# Power_Selection_-_Power_Path.net
KiCad netlist of a schematic drawn in Altium Designer
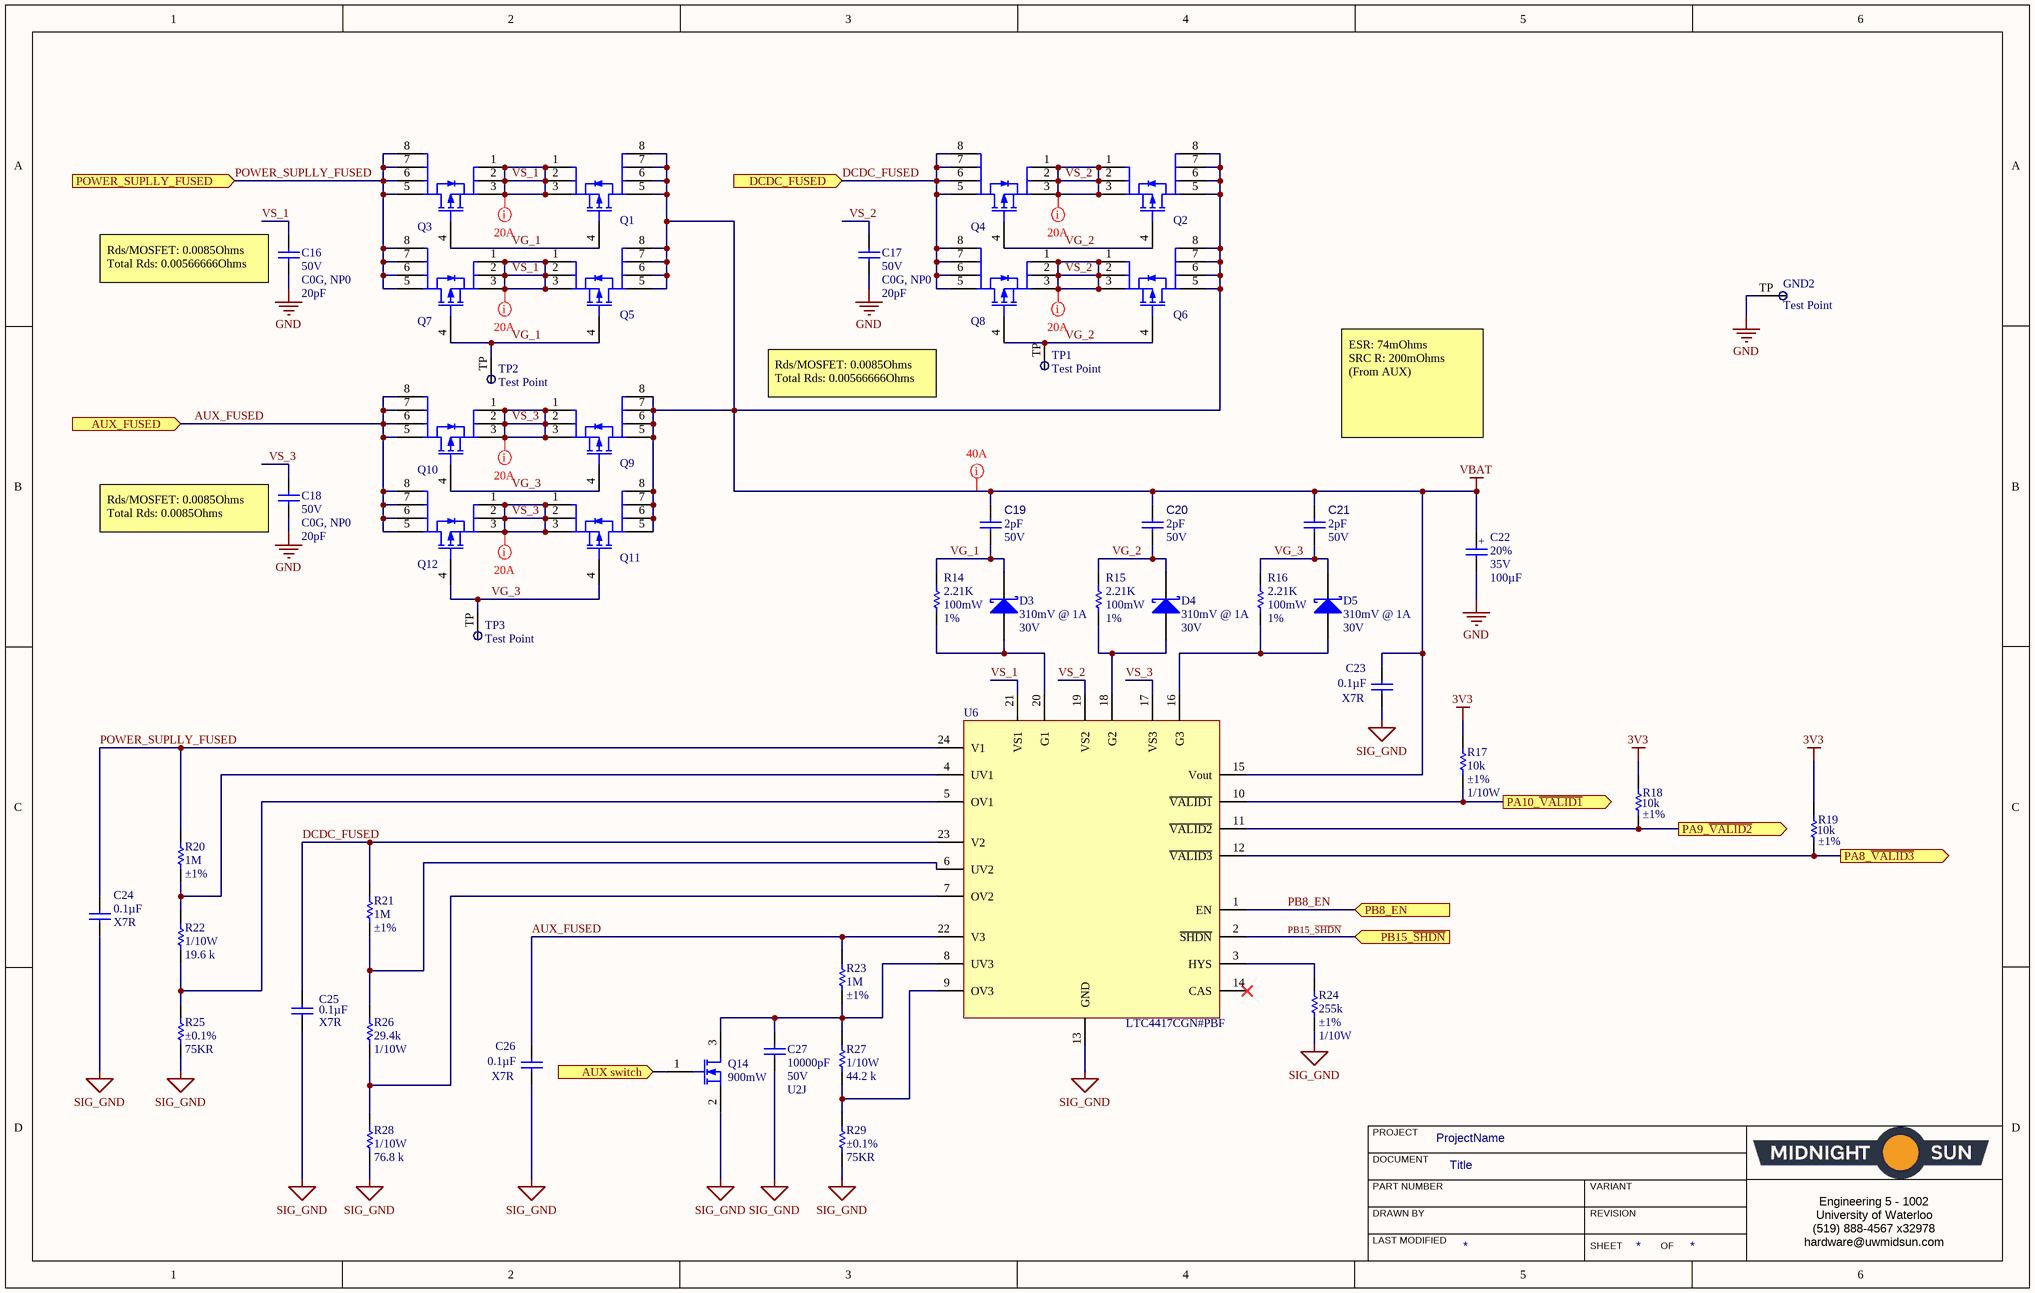
[diagram p0: Power Selection - Power Path.SchDoc]

(export (version "E")
  (design (tool "Eeschema 10.0.6"))
  (components
    (comp (ref "C16")
      (value "20pF")
      (footprint "CAP, 0603")
      (description "20pF ±5% 50V Ceramic Capacitor C0G, NP0 0603 (1608 Metric)")
      (fields
        (field (name "VOLTAGE") "50V")
        (field (name "TEMPERATURE COEFFICIENT") "C0G, NP0")
        (field (name "TOLERANCE") "5%")
        (field (name "Comment") "CAP CER 20PF 50V ±5% C0G/NP0 0603")
        (field (name "SOURCE") "Schematic Diagrams.SchLib")
      )
      (libsource (lib "University of Waterloo - Solar Car Team") (part "Symbol"))
    )
    (comp (ref "C17")
      (value "20pF")
      (footprint "CAP, 0603")
      (description "20pF ±5% 50V Ceramic Capacitor C0G, NP0 0603 (1608 Metric)")
      (fields
        (field (name "VOLTAGE") "50V")
        (field (name "TEMPERATURE COEFFICIENT") "C0G, NP0")
        (field (name "TOLERANCE") "5%")
        (field (name "Comment") "CAP CER 20PF 50V ±5% C0G/NP0 0603")
        (field (name "SOURCE") "Schematic Diagrams.SchLib")
      )
      (libsource (lib "University of Waterloo - Solar Car Team") (part "Symbol"))
    )
    (comp (ref "C18")
      (value "20pF")
      (footprint "CAP, 0603")
      (description "20pF ±5% 50V Ceramic Capacitor C0G, NP0 0603 (1608 Metric)")
      (fields
        (field (name "VOLTAGE") "50V")
        (field (name "TEMPERATURE COEFFICIENT") "C0G, NP0")
        (field (name "TOLERANCE") "5%")
        (field (name "Comment") "CAP CER 20PF 50V ±5% C0G/NP0 0603")
        (field (name "SOURCE") "Schematic Diagrams.SchLib")
      )
      (libsource (lib "University of Waterloo - Solar Car Team") (part "Symbol"))
    )
    (comp (ref "C19")
      (value "CAP CER 2PF 50V C0G 0603")
      (footprint "CAP, 0603")
      (description "2pF ±0.25pF 50V Ceramic Capacitor C0G, NP0 0603 (1608 Metric)")
      (fields (field (name "VOLTAGE RATING (DC)") "50V") (field (name "CAPACITANCE") "2pF"))
      (libsource (lib "University of Waterloo - Solar Car Team") (part "CAP-NP-2"))
    )
    (comp (ref "C20")
      (value "CAP CER 2PF 50V C0G 0603")
      (footprint "CAP, 0603")
      (description "2pF ±0.25pF 50V Ceramic Capacitor C0G, NP0 0603 (1608 Metric)")
      (fields (field (name "VOLTAGE RATING (DC)") "50V") (field (name "CAPACITANCE") "2pF"))
      (libsource (lib "University of Waterloo - Solar Car Team") (part "CAP-NP-2"))
    )
    (comp (ref "C21")
      (value "CAP CER 2PF 50V C0G 0603")
      (footprint "CAP, 0603")
      (description "2pF ±0.25pF 50V Ceramic Capacitor C0G, NP0 0603 (1608 Metric)")
      (fields (field (name "VOLTAGE RATING (DC)") "50V") (field (name "CAPACITANCE") "2pF"))
      (libsource (lib "University of Waterloo - Solar Car Team") (part "CAP-NP-2"))
    )
    (comp (ref "C22")
      (value "100µF")
      (footprint "CAP ALUM 6.3MM RADIAL SMD")
      (description "100µF 35V Aluminum Electrolytic Capacitors Radial, Can - SMD 2000 Hrs @ 85°C")
      (fields
        (field (name "TOLERANCE") "20%")
        (field (name "VOLTAGE RATING") "35V")
        (field (name "VOLTAGE") "35V")
        (field (name "Comment") "CAP ALUM 100UF 20% 35V SMD")
        (field (name "SOURCE") "Schematic Diagrams.SchLib")
      )
      (libsource (lib "") (part "Symbol_1"))
    )
    (comp (ref "C23")
      (value "CAP CER 0.1UF 50V 10% X7R 0603")
      (footprint "CAP, 0603")
      (description "0.10µF ±10% 50V Ceramic Capacitor X7R 0603 (1608 Metric)")
      (fields
        (field (name "TOLERANCE") "±10%")
        (field (name "CAPACITANCE") "0.1µF")
        (field (name "TEMPERATURE COEFFICIENT") "X7R")
        (field (name "VOLTAGE") "50V")
      )
      (libsource (lib "Schematic Diagrams") (part "CAP CER 0.1UF 50V 10% X7R 0603"))
    )
    (comp (ref "C24")
      (value "CAP CER 0.1UF 50V 10% X7R 0603")
      (footprint "CAP, 0603")
      (description "0.10µF ±10% 50V Ceramic Capacitor X7R 0603 (1608 Metric)")
      (fields
        (field (name "TOLERANCE") "±10%")
        (field (name "CAPACITANCE") "0.1µF")
        (field (name "TEMPERATURE COEFFICIENT") "X7R")
        (field (name "VOLTAGE") "50V")
      )
      (libsource (lib "Schematic Diagrams") (part "CAP CER 0.1UF 50V 10% X7R 0603"))
    )
    (comp (ref "C25")
      (value "CAP CER 0.1UF 50V 10% X7R 0603")
      (footprint "CAP, 0603")
      (description "0.10µF ±10% 50V Ceramic Capacitor X7R 0603 (1608 Metric)")
      (fields
        (field (name "TOLERANCE") "±10%")
        (field (name "CAPACITANCE") "0.1µF")
        (field (name "TEMPERATURE COEFFICIENT") "X7R")
        (field (name "VOLTAGE") "50V")
      )
      (libsource (lib "Schematic Diagrams") (part "CAP CER 0.1UF 50V 10% X7R 0603"))
    )
    (comp (ref "C26")
      (value "CAP CER 0.1UF 50V 10% X7R 0603")
      (footprint "CAP, 0603")
      (description "0.10µF ±10% 50V Ceramic Capacitor X7R 0603 (1608 Metric)")
      (fields
        (field (name "TOLERANCE") "±10%")
        (field (name "CAPACITANCE") "0.1µF")
        (field (name "TEMPERATURE COEFFICIENT") "X7R")
        (field (name "VOLTAGE") "50V")
      )
      (libsource (lib "Schematic Diagrams") (part "CAP CER 0.1UF 50V 10% X7R 0603"))
    )
    (comp (ref "C27")
      (value "CAP CER 10nF 50V 5% X7R 0603")
      (footprint "CAP, 0603")
      (description "10000pF ±5% 50V Ceramic Capacitor U2J 0603 (1608 Metric)")
      (fields
        (field (name "TOLERANCE") "±5%")
        (field (name "CAPACITANCE") "10000pF")
        (field (name "VOLTAGE") "50V")
        (field (name "TEMPERATURE COEFFICIENT") "U2J")
      )
      (libsource (lib "Schematic Diagrams") (part "CAP CER 10nF 50V 5% X7R 0603"))
    )
    (comp (ref "D3")
      (value "DIODE SCHOTTKY 30V 1A POWERDI123")
      (footprint "DIODE SCHOTTKY 30V 1A POWERDI123")
      (description "Diode Schottky 30V 1A Surface Mount PowerDI™ 123")
      (fields
        (field (name "MANUFACTURER") "Diodes Incorporated")
        (field (name "MANUFACTURER PART NUMBER") "DFLS130L-7")
        (field (name "VOLTAGE - FORWARD (VF) (MAX) @ IF") "310mV @ 1A")
        (field (name "VOLTAGE - DC REVERSE (VR) (MAX)") "30V")
      )
      (libsource (lib "Schematic Diagrams") (part "DIODE SCHOTTKY 30V 1A POWERDI123"))
    )
    (comp (ref "D4")
      (value "DIODE SCHOTTKY 30V 1A POWERDI123")
      (footprint "DIODE SCHOTTKY 30V 1A POWERDI123")
      (description "Diode Schottky 30V 1A Surface Mount PowerDI™ 123")
      (fields
        (field (name "MANUFACTURER") "Diodes Incorporated")
        (field (name "MANUFACTURER PART NUMBER") "DFLS130L-7")
        (field (name "VOLTAGE - FORWARD (VF) (MAX) @ IF") "310mV @ 1A")
        (field (name "VOLTAGE - DC REVERSE (VR) (MAX)") "30V")
      )
      (libsource (lib "Schematic Diagrams") (part "DIODE SCHOTTKY 30V 1A POWERDI123"))
    )
    (comp (ref "D5")
      (value "DIODE SCHOTTKY 30V 1A POWERDI123")
      (footprint "DIODE SCHOTTKY 30V 1A POWERDI123")
      (description "Diode Schottky 30V 1A Surface Mount PowerDI™ 123")
      (fields
        (field (name "MANUFACTURER") "Diodes Incorporated")
        (field (name "MANUFACTURER PART NUMBER") "DFLS130L-7")
        (field (name "VOLTAGE - FORWARD (VF) (MAX) @ IF") "310mV @ 1A")
        (field (name "VOLTAGE - DC REVERSE (VR) (MAX)") "30V")
      )
      (libsource (lib "Schematic Diagrams") (part "DIODE SCHOTTKY 30V 1A POWERDI123"))
    )
    (comp (ref "GND2")
      (value "Test Point")
      (footprint "Test Point")
      (libsource (lib "Schematic Diagrams") (part "Test Point"))
    )
    (comp (ref "Q1")
      (value "MOSFET P-CH PWR56 40V 4.9 MOHM")
      (footprint "PMOS PWR56 40V 4.9 MOHM")
      (description "P-Channel 16V 2.5A (Ta) 650mW (Ta) Surface Mount X2-DFN2015-3")
      (libsource (lib "Schematic Diagrams") (part "MOSFET P-CH PWR56 40V 4.9 MOHM"))
    )
    (comp (ref "Q2")
      (value "MOSFET P-CH PWR56 40V 4.9 MOHM")
      (footprint "PMOS PWR56 40V 4.9 MOHM")
      (description "P-Channel 16V 2.5A (Ta) 650mW (Ta) Surface Mount X2-DFN2015-3")
      (libsource (lib "Schematic Diagrams") (part "MOSFET P-CH PWR56 40V 4.9 MOHM"))
    )
    (comp (ref "Q3")
      (value "MOSFET P-CH PWR56 40V 4.9 MOHM")
      (footprint "PMOS PWR56 40V 4.9 MOHM")
      (description "P-Channel 16V 2.5A (Ta) 650mW (Ta) Surface Mount X2-DFN2015-3")
      (libsource (lib "Schematic Diagrams") (part "MOSFET P-CH PWR56 40V 4.9 MOHM"))
    )
    (comp (ref "Q4")
      (value "MOSFET P-CH PWR56 40V 4.9 MOHM")
      (footprint "PMOS PWR56 40V 4.9 MOHM")
      (description "P-Channel 16V 2.5A (Ta) 650mW (Ta) Surface Mount X2-DFN2015-3")
      (libsource (lib "Schematic Diagrams") (part "MOSFET P-CH PWR56 40V 4.9 MOHM"))
    )
    (comp (ref "Q5")
      (value "MOSFET P-CH PWR56 40V 4.9 MOHM")
      (footprint "PMOS PWR56 40V 4.9 MOHM")
      (description "P-Channel 16V 2.5A (Ta) 650mW (Ta) Surface Mount X2-DFN2015-3")
      (libsource (lib "Schematic Diagrams") (part "MOSFET P-CH PWR56 40V 4.9 MOHM"))
    )
    (comp (ref "Q6")
      (value "MOSFET P-CH PWR56 40V 4.9 MOHM")
      (footprint "PMOS PWR56 40V 4.9 MOHM")
      (description "P-Channel 16V 2.5A (Ta) 650mW (Ta) Surface Mount X2-DFN2015-3")
      (libsource (lib "Schematic Diagrams") (part "MOSFET P-CH PWR56 40V 4.9 MOHM"))
    )
    (comp (ref "Q7")
      (value "MOSFET P-CH PWR56 40V 4.9 MOHM")
      (footprint "PMOS PWR56 40V 4.9 MOHM")
      (description "P-Channel 16V 2.5A (Ta) 650mW (Ta) Surface Mount X2-DFN2015-3")
      (libsource (lib "Schematic Diagrams") (part "MOSFET P-CH PWR56 40V 4.9 MOHM"))
    )
    (comp (ref "Q8")
      (value "MOSFET P-CH PWR56 40V 4.9 MOHM")
      (footprint "PMOS PWR56 40V 4.9 MOHM")
      (description "P-Channel 16V 2.5A (Ta) 650mW (Ta) Surface Mount X2-DFN2015-3")
      (libsource (lib "Schematic Diagrams") (part "MOSFET P-CH PWR56 40V 4.9 MOHM"))
    )
    (comp (ref "Q9")
      (value "MOSFET P-CH PWR56 40V 4.9 MOHM")
      (footprint "PMOS PWR56 40V 4.9 MOHM")
      (description "P-Channel 16V 2.5A (Ta) 650mW (Ta) Surface Mount X2-DFN2015-3")
      (libsource (lib "Schematic Diagrams") (part "MOSFET P-CH PWR56 40V 4.9 MOHM"))
    )
    (comp (ref "Q10")
      (value "MOSFET P-CH PWR56 40V 4.9 MOHM")
      (footprint "PMOS PWR56 40V 4.9 MOHM")
      (description "P-Channel 16V 2.5A (Ta) 650mW (Ta) Surface Mount X2-DFN2015-3")
      (libsource (lib "Schematic Diagrams") (part "MOSFET P-CH PWR56 40V 4.9 MOHM"))
    )
    (comp (ref "Q11")
      (value "MOSFET P-CH PWR56 40V 4.9 MOHM")
      (footprint "PMOS PWR56 40V 4.9 MOHM")
      (description "P-Channel 16V 2.5A (Ta) 650mW (Ta) Surface Mount X2-DFN2015-3")
      (libsource (lib "Schematic Diagrams") (part "MOSFET P-CH PWR56 40V 4.9 MOHM"))
    )
    (comp (ref "Q12")
      (value "MOSFET P-CH PWR56 40V 4.9 MOHM")
      (footprint "PMOS PWR56 40V 4.9 MOHM")
      (description "P-Channel 16V 2.5A (Ta) 650mW (Ta) Surface Mount X2-DFN2015-3")
      (libsource (lib "Schematic Diagrams") (part "MOSFET P-CH PWR56 40V 4.9 MOHM"))
    )
    (comp (ref "Q14")
      (value "MOSFET N-CH 30V 6.2A 0.9W SOT-23")
      (footprint "MOSFET N-CH 30V 6.2A 0.9W SOT-23")
      (description "N-Channel 30V 6.2A (Ta) 900mW (Ta) Surface Mount SOT-23")
      (fields
        (field (name "MAX POWER DISSIPATION") "900mW")
        (field (name "MANUFACTURER") "Diodes")
        (field (name "MANUFACTURER PART NUMBER") "DMN3023L-7")
        (field (name "SOURCE") "Schematic Diagrams.SchLib")
      )
      (libsource (lib "University of Waterloo - Solar Car Team") (part "MOSFET N-CH 30V 6.2A 0.9W SOT-23"))
    )
    (comp (ref "R14")
      (value "2.21K")
      (footprint "RES, 0603")
      (fields
        (field (name "MANUFACTURER") "Yageo")
        (field (name "MANUFACTURER PART NUMBER") "AC0603FR-072K21L")
        (field (name "TOLERANCE") "1%")
        (field (name "MAX POWER DISSIPATION") "100mW")
      )
      (libsource (lib "Schematic Diagrams") (part "RES 2.21K OHM 1% 1/10W 0603"))
    )
    (comp (ref "R15")
      (value "2.21K")
      (footprint "RES, 0603")
      (fields
        (field (name "MANUFACTURER") "Yageo")
        (field (name "MANUFACTURER PART NUMBER") "AC0603FR-072K21L")
        (field (name "TOLERANCE") "1%")
        (field (name "MAX POWER DISSIPATION") "100mW")
      )
      (libsource (lib "Schematic Diagrams") (part "RES 2.21K OHM 1% 1/10W 0603"))
    )
    (comp (ref "R16")
      (value "2.21K")
      (footprint "RES, 0603")
      (fields
        (field (name "MANUFACTURER") "Yageo")
        (field (name "MANUFACTURER PART NUMBER") "AC0603FR-072K21L")
        (field (name "TOLERANCE") "1%")
        (field (name "MAX POWER DISSIPATION") "100mW")
      )
      (libsource (lib "Schematic Diagrams") (part "RES 2.21K OHM 1% 1/10W 0603"))
    )
    (comp (ref "R17")
      (value "RES 10K OHM 1% 1/10W 0603")
      (footprint "RES, 0603")
      (description "RES SMD 10K OHM 1% 1/10W 0603")
      (fields
        (field (name "RESISTANCE") "10k")
        (field (name "TOLERANCE") "±1%")
        (field (name "POWER") "1/10W")
      )
      (libsource (lib "Schematic Diagrams") (part "RES 10K OHM 1% 1/10W 0603"))
    )
    (comp (ref "R18")
      (value "RES 10K OHM 1% 1/10W 0603")
      (footprint "RES, 0603")
      (description "RES SMD 10K OHM 1% 1/10W 0603")
      (fields (field (name "RESISTANCE") "10k") (field (name "TOLERANCE") "±1%"))
      (libsource (lib "Schematic Diagrams") (part "RES 10K OHM 1% 1/10W 0603"))
    )
    (comp (ref "R19")
      (value "RES 10K OHM 1% 1/10W 0603")
      (footprint "RES, 0603")
      (description "RES SMD 10K OHM 1% 1/10W 0603")
      (fields (field (name "RESISTANCE") "10k") (field (name "TOLERANCE") "±1%"))
      (libsource (lib "Schematic Diagrams") (part "RES 10K OHM 1% 1/10W 0603"))
    )
    (comp (ref "R20")
      (value "RES 1M OHM 1% 1/10W 0603")
      (footprint "RES, 0603")
      (description "1M Ohm ±1% 0.1W, 1/10W Chip Resistor 0603 (1608 Metric) Moisture Resistant Thick Film")
      (fields (field (name "RESISTANCE (OHMS)") "1M") (field (name "TOLERANCE") "±1%"))
      (libsource (lib "Schematic Diagrams") (part "RES 1M OHM 1% 1/10W 0603"))
    )
    (comp (ref "R21")
      (value "RES 1M OHM 1% 1/10W 0603")
      (footprint "RES, 0603")
      (description "1M Ohm ±1% 0.1W, 1/10W Chip Resistor 0603 (1608 Metric) Moisture Resistant Thick Film")
      (fields (field (name "RESISTANCE (OHMS)") "1M") (field (name "TOLERANCE") "±1%"))
      (libsource (lib "Schematic Diagrams") (part "RES 1M OHM 1% 1/10W 0603"))
    )
    (comp (ref "R22")
      (value "RES 19.6K OHM 1% 1/10W 0603")
      (footprint "RES, 0603")
      (description "19.6 kOhms ±1% 0.1W, 1/10W Chip Resistor 0603 (1608 Metric) Automotive AEC-Q200 Thick Film")
      (fields (field (name "POWER (WATTS)") "1/10W") (field (name "RESISTANCE") "19.6 k"))
      (libsource (lib "Schematic Diagrams") (part "RES 19.6K OHM 1% 1/10W 0603"))
    )
    (comp (ref "R23")
      (value "RES 1M OHM 1% 1/10W 0603")
      (footprint "RES, 0603")
      (description "1M Ohm ±1% 0.1W, 1/10W Chip Resistor 0603 (1608 Metric) Moisture Resistant Thick Film")
      (fields (field (name "RESISTANCE (OHMS)") "1M") (field (name "TOLERANCE") "±1%"))
      (libsource (lib "Schematic Diagrams") (part "RES 1M OHM 1% 1/10W 0603"))
    )
    (comp (ref "R24")
      (value "RES 255K OHM 1% 1/10W 0603")
      (footprint "RES, 0603")
      (description "255k Ohm ±1% 0.1W, 1/10W Chip Resistor 0603 (1608 Metric) Moisture Resistant Thick Film")
      (fields
        (field (name "RESISTANCE (OHMS)") "255k")
        (field (name "TOLERANCE") "±1%")
        (field (name "POWER (WATTS)") "1/10W")
      )
      (libsource (lib "Schematic Diagrams") (part "RES 255K OHM 1% 1/10W 0603"))
    )
    (comp (ref "R25")
      (value "75KR")
      (footprint "RES, 0603")
      (description "75 kOhms ±0.1% 0.1W, 1/10W Chip Resistor 0603 (1608 Metric) Automotive AEC-Q200 Thin Film")
      (fields
        (field (name "MANUFACTURER") "Panasonic Electronic Components")
        (field (name "MANUFACTURER PART NUMBER") "AC0603FR-0775RL")
        (field (name "TOLERANCE") "±0.1%")
      )
      (libsource (lib "") (part "RES SMD 75K OHM 0.1% 1/10W 0603_1"))
    )
    (comp (ref "R26")
      (value "RES 29.4K OHM 1% 1/10W 0603")
      (footprint "RES, 0603")
      (description "29.4k Ohm ±1% 0.1W, 1/10W Chip Resistor 0603 (1608 Metric) Moisture Resistant Thick Film")
      (fields
        (field (name "TOLERANCE") "±1%")
        (field (name "RESISTANCE (OHMS)") "29.4k")
        (field (name "POWER (WATTS)") "1/10W")
      )
      (libsource (lib "Schematic Diagrams") (part "RES 29.4K OHM 1% 1/10W 0603"))
    )
    (comp (ref "R27")
      (value "RES SMD 44.2K OHM 1% 1/10W 0603")
      (footprint "RES, 0603")
      (description "44.2 kOhms ±1% 0.1W, 1/10W Chip Resistor 0603 (1608 Metric) Automotive AEC-Q200 Thick Film")
      (fields (field (name "POWER (WATTS)") "1/10W") (field (name "RESISTANCE") "44.2 k"))
      (libsource (lib "Schematic Diagrams") (part "RES SMD 44.2K OHM 1% 1/10W 0603"))
    )
    (comp (ref "R28")
      (value "RES 76.8K OHM 1% 1/10W 0603")
      (footprint "RES, 0603")
      (description "76.8 kOhms ±1% 0.1W, 1/10W Chip Resistor 0603 (1608 Metric) Automotive AEC-Q200 Thick Film")
      (fields (field (name "POWER (WATTS)") "1/10W") (field (name "RESISTANCE") "76.8 k"))
      (libsource (lib "Schematic Diagrams") (part "RES 76.8K OHM 1% 1/10W 0603"))
    )
    (comp (ref "R29")
      (value "75KR")
      (footprint "RES, 0603")
      (description "75 kOhms ±0.1% 0.1W, 1/10W Chip Resistor 0603 (1608 Metric) Automotive AEC-Q200 Thin Film")
      (fields
        (field (name "MANUFACTURER") "Panasonic Electronic Components")
        (field (name "MANUFACTURER PART NUMBER") "AC0603FR-0775RL")
        (field (name "TOLERANCE") "±0.1%")
      )
      (libsource (lib "Schematic Diagrams") (part "RES SMD 75K OHM 0.1% 1/10W 0603"))
    )
    (comp (ref "TP1")
      (value "Test Point")
      (footprint "Test Point")
      (libsource (lib "Schematic Diagrams") (part "Test Point"))
    )
    (comp (ref "TP2")
      (value "Test Point")
      (footprint "Test Point")
      (libsource (lib "Schematic Diagrams") (part "Test Point"))
    )
    (comp (ref "TP3")
      (value "Test Point")
      (footprint "Test Point")
      (libsource (lib "Schematic Diagrams") (part "Test Point"))
    )
    (comp (ref "U6")
      (value "IC OR CONTROLLER SOURCE SELECT 24SSOP")
      (footprint "IC OR CTRLR SRC SELECT 24SSOP")
      (description "OR Controller Source Selector Switch P-Channel 3:1 24-SSOP")
      (fields (field (name "MANUFACTURER PART NUMBER 1") "LTC4417CGN#PBF"))
      (libsource (lib "Schematic Diagrams") (part "IC OR CONTROLLER SOURCE SELECT 24SSOP"))
    )
  )
  (nets
    (net (code "1") (name "/AUX switch") (class "Default")
      (node (ref "Q14") (pin "1") (pinfunction "G_1") (pintype "passive"))
    )
    (net (code "2") (name "/AUX_FUSED") (class "Default")
      (node (ref "C26") (pin "1") (pinfunction "1_1") (pintype "passive"))
      (node (ref "Q10") (pin "5") (pinfunction "D_5") (pintype "passive"))
      (node (ref "Q10") (pin "6") (pinfunction "D_6") (pintype "passive"))
      (node (ref "Q10") (pin "7") (pinfunction "D_7") (pintype "passive"))
      (node (ref "Q10") (pin "8") (pinfunction "D_8") (pintype "passive"))
      (node (ref "Q12") (pin "5") (pinfunction "D_5") (pintype "passive"))
      (node (ref "Q12") (pin "6") (pinfunction "D_6") (pintype "passive"))
      (node (ref "Q12") (pin "7") (pinfunction "D_7") (pintype "passive"))
      (node (ref "Q12") (pin "8") (pinfunction "D_8") (pintype "passive"))
      (node (ref "R23") (pin "1") (pinfunction "1_1") (pintype "passive"))
      (node (ref "U6") (pin "22") (pinfunction "V3_22") (pintype "passive"))
    )
    (net (code "3") (name "/DCDC_FUSED") (class "Default")
      (node (ref "C25") (pin "1") (pinfunction "1_1") (pintype "passive"))
      (node (ref "Q4") (pin "5") (pinfunction "D_5") (pintype "passive"))
      (node (ref "Q4") (pin "6") (pinfunction "D_6") (pintype "passive"))
      (node (ref "Q4") (pin "7") (pinfunction "D_7") (pintype "passive"))
      (node (ref "Q4") (pin "8") (pinfunction "D_8") (pintype "passive"))
      (node (ref "Q8") (pin "5") (pinfunction "D_5") (pintype "passive"))
      (node (ref "Q8") (pin "6") (pinfunction "D_6") (pintype "passive"))
      (node (ref "Q8") (pin "7") (pinfunction "D_7") (pintype "passive"))
      (node (ref "Q8") (pin "8") (pinfunction "D_8") (pintype "passive"))
      (node (ref "R21") (pin "1") (pinfunction "1_1") (pintype "passive"))
      (node (ref "U6") (pin "23") (pinfunction "V2_23") (pintype "passive"))
    )
    (net (code "4") (name "/PA8_~{VALID3}") (class "Default")
      (node (ref "R19") (pin "2") (pinfunction "2_2") (pintype "passive"))
      (node (ref "U6") (pin "12") (pinfunction "~{VALID3}_12") (pintype "passive"))
    )
    (net (code "5") (name "/PA9_~{VALID2}") (class "Default")
      (node (ref "R18") (pin "2") (pinfunction "2_2") (pintype "passive"))
      (node (ref "U6") (pin "11") (pinfunction "~{VALID2}_11") (pintype "passive"))
    )
    (net (code "6") (name "/PA10_~{VALID1}") (class "Default")
      (node (ref "R17") (pin "2") (pinfunction "2_2") (pintype "passive"))
      (node (ref "U6") (pin "10") (pinfunction "~{VALID1}_10") (pintype "passive"))
    )
    (net (code "7") (name "/PB8_EN") (class "Default")
      (node (ref "U6") (pin "1") (pinfunction "EN_1") (pintype "passive"))
    )
    (net (code "8") (name "/PB15_~{SHDN}") (class "Default")
      (node (ref "U6") (pin "2") (pinfunction "~{SHDN}_2") (pintype "passive"))
    )
    (net (code "9") (name "/POWER_SUPLLY_FUSED") (class "Default")
      (node (ref "C24") (pin "1") (pinfunction "1_1") (pintype "passive"))
      (node (ref "Q3") (pin "5") (pinfunction "D_5") (pintype "passive"))
      (node (ref "Q3") (pin "6") (pinfunction "D_6") (pintype "passive"))
      (node (ref "Q3") (pin "7") (pinfunction "D_7") (pintype "passive"))
      (node (ref "Q3") (pin "8") (pinfunction "D_8") (pintype "passive"))
      (node (ref "Q7") (pin "5") (pinfunction "D_5") (pintype "passive"))
      (node (ref "Q7") (pin "6") (pinfunction "D_6") (pintype "passive"))
      (node (ref "Q7") (pin "7") (pinfunction "D_7") (pintype "passive"))
      (node (ref "Q7") (pin "8") (pinfunction "D_8") (pintype "passive"))
      (node (ref "R20") (pin "1") (pinfunction "1_1") (pintype "passive"))
      (node (ref "U6") (pin "24") (pinfunction "V1_24") (pintype "passive"))
    )
    (net (code "10") (name "/VG_1") (class "Default")
      (node (ref "C19") (pin "1") (pinfunction "1_1") (pintype "passive"))
      (node (ref "D3") (pin "2") (pinfunction "K_2") (pintype "passive"))
      (node (ref "Q1") (pin "4") (pinfunction "G_4") (pintype "passive"))
      (node (ref "Q3") (pin "4") (pinfunction "G_4") (pintype "passive"))
      (node (ref "Q5") (pin "4") (pinfunction "G_4") (pintype "passive"))
      (node (ref "Q7") (pin "4") (pinfunction "G_4") (pintype "passive"))
      (node (ref "R14") (pin "1") (pinfunction "1_1") (pintype "passive"))
      (node (ref "TP2") (pin "TP") (pinfunction "1_TP") (pintype "passive"))
    )
    (net (code "11") (name "/VG_2") (class "Default")
      (node (ref "C20") (pin "1") (pinfunction "1_1") (pintype "passive"))
      (node (ref "D4") (pin "2") (pinfunction "K_2") (pintype "passive"))
      (node (ref "Q2") (pin "4") (pinfunction "G_4") (pintype "passive"))
      (node (ref "Q4") (pin "4") (pinfunction "G_4") (pintype "passive"))
      (node (ref "Q6") (pin "4") (pinfunction "G_4") (pintype "passive"))
      (node (ref "Q8") (pin "4") (pinfunction "G_4") (pintype "passive"))
      (node (ref "R15") (pin "1") (pinfunction "1_1") (pintype "passive"))
      (node (ref "TP1") (pin "TP") (pinfunction "1_TP") (pintype "passive"))
    )
    (net (code "12") (name "/VG_3") (class "Default")
      (node (ref "C21") (pin "1") (pinfunction "1_1") (pintype "passive"))
      (node (ref "D5") (pin "2") (pinfunction "K_2") (pintype "passive"))
      (node (ref "Q10") (pin "4") (pinfunction "G_4") (pintype "passive"))
      (node (ref "Q11") (pin "4") (pinfunction "G_4") (pintype "passive"))
      (node (ref "Q12") (pin "4") (pinfunction "G_4") (pintype "passive"))
      (node (ref "Q9") (pin "4") (pinfunction "G_4") (pintype "passive"))
      (node (ref "R16") (pin "1") (pinfunction "1_1") (pintype "passive"))
      (node (ref "TP3") (pin "TP") (pinfunction "1_TP") (pintype "passive"))
    )
    (net (code "13") (name "/VS_1") (class "Default")
      (node (ref "C16") (pin "1") (pinfunction "1_1") (pintype "passive"))
      (node (ref "Q1") (pin "1") (pinfunction "S_1") (pintype "passive"))
      (node (ref "Q1") (pin "2") (pinfunction "S_2") (pintype "passive"))
      (node (ref "Q1") (pin "3") (pinfunction "S_3") (pintype "passive"))
      (node (ref "Q3") (pin "1") (pinfunction "S_1") (pintype "passive"))
      (node (ref "Q3") (pin "2") (pinfunction "S_2") (pintype "passive"))
      (node (ref "Q3") (pin "3") (pinfunction "S_3") (pintype "passive"))
      (node (ref "Q5") (pin "1") (pinfunction "S_1") (pintype "passive"))
      (node (ref "Q5") (pin "2") (pinfunction "S_2") (pintype "passive"))
      (node (ref "Q5") (pin "3") (pinfunction "S_3") (pintype "passive"))
      (node (ref "Q7") (pin "1") (pinfunction "S_1") (pintype "passive"))
      (node (ref "Q7") (pin "2") (pinfunction "S_2") (pintype "passive"))
      (node (ref "Q7") (pin "3") (pinfunction "S_3") (pintype "passive"))
      (node (ref "U6") (pin "21") (pinfunction "VS1_21") (pintype "passive"))
    )
    (net (code "14") (name "/VS_2") (class "Default")
      (node (ref "C17") (pin "1") (pinfunction "1_1") (pintype "passive"))
      (node (ref "Q2") (pin "1") (pinfunction "S_1") (pintype "passive"))
      (node (ref "Q2") (pin "2") (pinfunction "S_2") (pintype "passive"))
      (node (ref "Q2") (pin "3") (pinfunction "S_3") (pintype "passive"))
      (node (ref "Q4") (pin "1") (pinfunction "S_1") (pintype "passive"))
      (node (ref "Q4") (pin "2") (pinfunction "S_2") (pintype "passive"))
      (node (ref "Q4") (pin "3") (pinfunction "S_3") (pintype "passive"))
      (node (ref "Q6") (pin "1") (pinfunction "S_1") (pintype "passive"))
      (node (ref "Q6") (pin "2") (pinfunction "S_2") (pintype "passive"))
      (node (ref "Q6") (pin "3") (pinfunction "S_3") (pintype "passive"))
      (node (ref "Q8") (pin "1") (pinfunction "S_1") (pintype "passive"))
      (node (ref "Q8") (pin "2") (pinfunction "S_2") (pintype "passive"))
      (node (ref "Q8") (pin "3") (pinfunction "S_3") (pintype "passive"))
      (node (ref "U6") (pin "19") (pinfunction "VS2_19") (pintype "passive"))
    )
    (net (code "15") (name "/VS_3") (class "Default")
      (node (ref "C18") (pin "1") (pinfunction "1_1") (pintype "passive"))
      (node (ref "Q10") (pin "1") (pinfunction "S_1") (pintype "passive"))
      (node (ref "Q10") (pin "2") (pinfunction "S_2") (pintype "passive"))
      (node (ref "Q10") (pin "3") (pinfunction "S_3") (pintype "passive"))
      (node (ref "Q11") (pin "1") (pinfunction "S_1") (pintype "passive"))
      (node (ref "Q11") (pin "2") (pinfunction "S_2") (pintype "passive"))
      (node (ref "Q11") (pin "3") (pinfunction "S_3") (pintype "passive"))
      (node (ref "Q12") (pin "1") (pinfunction "S_1") (pintype "passive"))
      (node (ref "Q12") (pin "2") (pinfunction "S_2") (pintype "passive"))
      (node (ref "Q12") (pin "3") (pinfunction "S_3") (pintype "passive"))
      (node (ref "Q9") (pin "1") (pinfunction "S_1") (pintype "passive"))
      (node (ref "Q9") (pin "2") (pinfunction "S_2") (pintype "passive"))
      (node (ref "Q9") (pin "3") (pinfunction "S_3") (pintype "passive"))
      (node (ref "U6") (pin "17") (pinfunction "VS3_17") (pintype "passive"))
    )
    (net (code "16") (name "3V3") (class "Default")
      (node (ref "R17") (pin "1") (pinfunction "1_1") (pintype "passive"))
      (node (ref "R18") (pin "1") (pinfunction "1_1") (pintype "passive"))
      (node (ref "R19") (pin "1") (pinfunction "1_1") (pintype "passive"))
    )
    (net (code "17") (name "GND") (class "Default")
      (node (ref "C16") (pin "2") (pinfunction "2_2") (pintype "passive"))
      (node (ref "C17") (pin "2") (pinfunction "2_2") (pintype "passive"))
      (node (ref "C18") (pin "2") (pinfunction "2_2") (pintype "passive"))
      (node (ref "C22") (pin "2") (pinfunction "2_2") (pintype "passive"))
      (node (ref "GND2") (pin "TP") (pinfunction "1_TP") (pintype "passive"))
    )
    (net (code "18") (name "Net-(D3-A)") (class "Default")
      (node (ref "D3") (pin "1") (pinfunction "A_1") (pintype "passive"))
      (node (ref "R14") (pin "2") (pinfunction "2_2") (pintype "passive"))
      (node (ref "U6") (pin "20") (pinfunction "G1_20") (pintype "passive"))
    )
    (net (code "19") (name "Net-(D4-A)") (class "Default")
      (node (ref "D4") (pin "1") (pinfunction "A_1") (pintype "passive"))
      (node (ref "R15") (pin "2") (pinfunction "2_2") (pintype "passive"))
      (node (ref "U6") (pin "18") (pinfunction "G2_18") (pintype "passive"))
    )
    (net (code "20") (name "Net-(D5-A)") (class "Default")
      (node (ref "D5") (pin "1") (pinfunction "A_1") (pintype "passive"))
      (node (ref "R16") (pin "2") (pinfunction "2_2") (pintype "passive"))
      (node (ref "U6") (pin "16") (pinfunction "G3_16") (pintype "passive"))
    )
    (net (code "21") (name "Net-(Q14-D)") (class "Default")
      (node (ref "C27") (pin "1") (pinfunction "1_1") (pintype "passive"))
      (node (ref "Q14") (pin "3") (pinfunction "D_3") (pintype "passive"))
      (node (ref "R23") (pin "2") (pinfunction "2_2") (pintype "passive"))
      (node (ref "R27") (pin "1") (pinfunction "1_1") (pintype "passive"))
      (node (ref "U6") (pin "8") (pinfunction "UV3_8") (pintype "passive"))
    )
    (net (code "22") (name "Net-(U6-HYS)") (class "Default")
      (node (ref "R24") (pin "1") (pinfunction "1_1") (pintype "passive"))
      (node (ref "U6") (pin "3") (pinfunction "HYS_3") (pintype "passive"))
    )
    (net (code "23") (name "Net-(U6-OV1)") (class "Default")
      (node (ref "R22") (pin "2") (pinfunction "2_2") (pintype "passive"))
      (node (ref "R25") (pin "2") (pinfunction "2_2") (pintype "passive"))
      (node (ref "U6") (pin "5") (pinfunction "OV1_5") (pintype "passive"))
    )
    (net (code "24") (name "Net-(U6-OV2)") (class "Default")
      (node (ref "R26") (pin "2") (pinfunction "2_2") (pintype "passive"))
      (node (ref "R28") (pin "1") (pinfunction "1_1") (pintype "passive"))
      (node (ref "U6") (pin "7") (pinfunction "OV2_7") (pintype "passive"))
    )
    (net (code "25") (name "Net-(U6-OV3)") (class "Default")
      (node (ref "R27") (pin "2") (pinfunction "2_2") (pintype "passive"))
      (node (ref "R29") (pin "1") (pinfunction "1_1") (pintype "passive"))
      (node (ref "U6") (pin "9") (pinfunction "OV3_9") (pintype "passive"))
    )
    (net (code "26") (name "Net-(U6-UV1)") (class "Default")
      (node (ref "R20") (pin "2") (pinfunction "2_2") (pintype "passive"))
      (node (ref "R22") (pin "1") (pinfunction "1_1") (pintype "passive"))
      (node (ref "U6") (pin "4") (pinfunction "UV1_4") (pintype "passive"))
    )
    (net (code "27") (name "Net-(U6-UV2)") (class "Default")
      (node (ref "R21") (pin "2") (pinfunction "2_2") (pintype "passive"))
      (node (ref "R26") (pin "1") (pinfunction "1_1") (pintype "passive"))
      (node (ref "U6") (pin "6") (pinfunction "UV2_6") (pintype "passive"))
    )
    (net (code "28") (name "SIG_GND") (class "Default")
      (node (ref "C23") (pin "2") (pinfunction "2_2") (pintype "passive"))
      (node (ref "C24") (pin "2") (pinfunction "2_2") (pintype "passive"))
      (node (ref "C25") (pin "2") (pinfunction "2_2") (pintype "passive"))
      (node (ref "C26") (pin "2") (pinfunction "2_2") (pintype "passive"))
      (node (ref "C27") (pin "2") (pinfunction "2_2") (pintype "passive"))
      (node (ref "Q14") (pin "2") (pinfunction "S_2") (pintype "passive"))
      (node (ref "R24") (pin "2") (pinfunction "2_2") (pintype "passive"))
      (node (ref "R25") (pin "1") (pinfunction "1_1") (pintype "passive"))
      (node (ref "R28") (pin "2") (pinfunction "2_2") (pintype "passive"))
      (node (ref "R29") (pin "2") (pinfunction "2_2") (pintype "passive"))
      (node (ref "U6") (pin "13") (pinfunction "GND_13") (pintype "passive"))
    )
    (net (code "29") (name "VBAT") (class "Default")
      (node (ref "C19") (pin "2") (pinfunction "2_2") (pintype "passive"))
      (node (ref "C20") (pin "2") (pinfunction "2_2") (pintype "passive"))
      (node (ref "C21") (pin "2") (pinfunction "2_2") (pintype "passive"))
      (node (ref "C22") (pin "1") (pinfunction "1_1") (pintype "passive"))
      (node (ref "C23") (pin "1") (pinfunction "1_1") (pintype "passive"))
      (node (ref "Q1") (pin "5") (pinfunction "D_5") (pintype "passive"))
      (node (ref "Q1") (pin "6") (pinfunction "D_6") (pintype "passive"))
      (node (ref "Q1") (pin "7") (pinfunction "D_7") (pintype "passive"))
      (node (ref "Q1") (pin "8") (pinfunction "D_8") (pintype "passive"))
      (node (ref "Q11") (pin "5") (pinfunction "D_5") (pintype "passive"))
      (node (ref "Q11") (pin "6") (pinfunction "D_6") (pintype "passive"))
      (node (ref "Q11") (pin "7") (pinfunction "D_7") (pintype "passive"))
      (node (ref "Q11") (pin "8") (pinfunction "D_8") (pintype "passive"))
      (node (ref "Q2") (pin "5") (pinfunction "D_5") (pintype "passive"))
      (node (ref "Q2") (pin "6") (pinfunction "D_6") (pintype "passive"))
      (node (ref "Q2") (pin "7") (pinfunction "D_7") (pintype "passive"))
      (node (ref "Q2") (pin "8") (pinfunction "D_8") (pintype "passive"))
      (node (ref "Q5") (pin "5") (pinfunction "D_5") (pintype "passive"))
      (node (ref "Q5") (pin "6") (pinfunction "D_6") (pintype "passive"))
      (node (ref "Q5") (pin "7") (pinfunction "D_7") (pintype "passive"))
      (node (ref "Q5") (pin "8") (pinfunction "D_8") (pintype "passive"))
      (node (ref "Q6") (pin "5") (pinfunction "D_5") (pintype "passive"))
      (node (ref "Q6") (pin "6") (pinfunction "D_6") (pintype "passive"))
      (node (ref "Q6") (pin "7") (pinfunction "D_7") (pintype "passive"))
      (node (ref "Q6") (pin "8") (pinfunction "D_8") (pintype "passive"))
      (node (ref "Q9") (pin "5") (pinfunction "D_5") (pintype "passive"))
      (node (ref "Q9") (pin "6") (pinfunction "D_6") (pintype "passive"))
      (node (ref "Q9") (pin "7") (pinfunction "D_7") (pintype "passive"))
      (node (ref "Q9") (pin "8") (pinfunction "D_8") (pintype "passive"))
      (node (ref "U6") (pin "15") (pinfunction "Vout_15") (pintype "passive"))
    )
    (net (code "30") (name "unconnected-(U6-CAS-Pad14)") (class "Default")
      (node (ref "U6") (pin "14") (pinfunction "CAS_14") (pintype "passive+no_connect"))
    )
  )
)
